# USB3_0HUB_1.net
KiCad netlist of a schematic drawn in Altium Designer
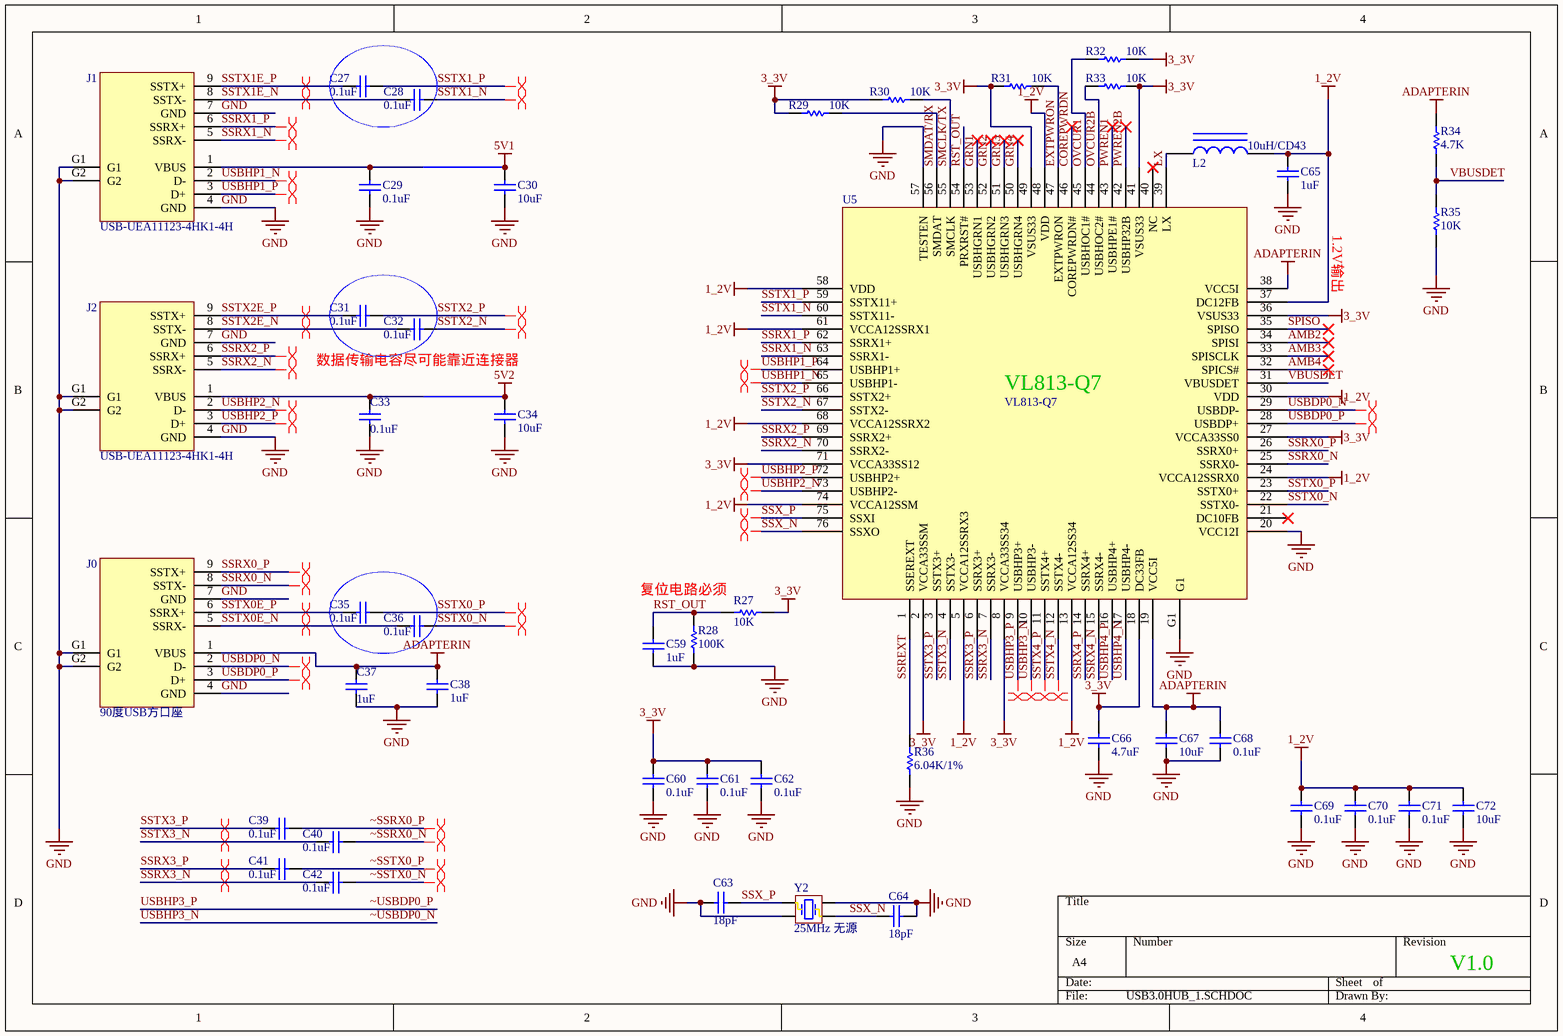
[diagram p0: USB3.0HUB_1.SCHDOC]

(export (version "E")
  (design (tool "Eeschema 10.0.6"))
  (components
    (comp (ref "C27")
      (value "0.1uF")
      (footprint "0603C")
      (description "Capacitor")
      (fields (field (name "PUBLISHER") "Altium Limited"))
      (libsource (lib "JL_SCH") (part "Cap"))
    )
    (comp (ref "C28")
      (value "0.1uF")
      (footprint "0603C")
      (description "Capacitor")
      (fields (field (name "PUBLISHER") "Altium Limited"))
      (libsource (lib "JL_SCH") (part "Cap"))
    )
    (comp (ref "C29")
      (value "0.1uF")
      (footprint "0603C")
      (description "Capacitor")
      (fields (field (name "PUBLISHER") "Altium Limited"))
      (libsource (lib "JL_SCH") (part "Cap"))
    )
    (comp (ref "C30")
      (value "10uF")
      (footprint "0805C")
      (description "Capacitor")
      (fields (field (name "PUBLISHER") "Altium Limited"))
      (libsource (lib "JL_SCH") (part "Cap"))
    )
    (comp (ref "C31")
      (value "0.1uF")
      (footprint "0603C")
      (description "Capacitor")
      (fields (field (name "PUBLISHER") "Altium Limited"))
      (libsource (lib "JL_SCH") (part "Cap"))
    )
    (comp (ref "C32")
      (value "0.1uF")
      (footprint "0603C")
      (description "Capacitor")
      (fields (field (name "PUBLISHER") "Altium Limited"))
      (libsource (lib "JL_SCH") (part "Cap"))
    )
    (comp (ref "C33")
      (value "0.1uF")
      (footprint "0603C")
      (description "Capacitor")
      (fields (field (name "PUBLISHER") "Altium Limited"))
      (libsource (lib "JL_SCH") (part "Cap"))
    )
    (comp (ref "C34")
      (value "10uF")
      (footprint "0805C")
      (description "Capacitor")
      (fields (field (name "PUBLISHER") "Altium Limited"))
      (libsource (lib "JL_SCH") (part "Cap"))
    )
    (comp (ref "C35")
      (value "0.1uF")
      (footprint "0603C")
      (description "Capacitor")
      (fields (field (name "PUBLISHER") "Altium Limited"))
      (libsource (lib "JL_SCH") (part "Cap"))
    )
    (comp (ref "C36")
      (value "0.1uF")
      (footprint "0603C")
      (description "Capacitor")
      (fields (field (name "PUBLISHER") "Altium Limited"))
      (libsource (lib "JL_SCH") (part "Cap"))
    )
    (comp (ref "C37")
      (value "1uF")
      (footprint "0603C")
      (description "Capacitor")
      (fields (field (name "PUBLISHER") "Altium Limited"))
      (libsource (lib "JL_SCH") (part "Cap"))
    )
    (comp (ref "C38")
      (value "1uF")
      (footprint "0603C")
      (description "Capacitor")
      (fields (field (name "PUBLISHER") "Altium Limited"))
      (libsource (lib "JL_SCH") (part "Cap"))
    )
    (comp (ref "C39")
      (value "0.1uF")
      (footprint "0603C")
      (description "Capacitor")
      (fields (field (name "PUBLISHER") "Altium Limited"))
      (libsource (lib "JL_SCH") (part "Cap"))
    )
    (comp (ref "C40")
      (value "0.1uF")
      (footprint "0603C")
      (description "Capacitor")
      (fields (field (name "PUBLISHER") "Altium Limited"))
      (libsource (lib "JL_SCH") (part "Cap"))
    )
    (comp (ref "C41")
      (value "0.1uF")
      (footprint "0603C")
      (description "Capacitor")
      (fields (field (name "PUBLISHER") "Altium Limited"))
      (libsource (lib "JL_SCH") (part "Cap"))
    )
    (comp (ref "C42")
      (value "0.1uF")
      (footprint "0603C")
      (description "Capacitor")
      (fields (field (name "PUBLISHER") "Altium Limited"))
      (libsource (lib "JL_SCH") (part "Cap"))
    )
    (comp (ref "C59")
      (value "1uF")
      (footprint "0603C")
      (description "Capacitor")
      (fields (field (name "PUBLISHER") "Altium Limited"))
      (libsource (lib "JL_SCH") (part "Cap"))
    )
    (comp (ref "C60")
      (value "0.1uF")
      (footprint "0603C")
      (description "Capacitor")
      (fields (field (name "PUBLISHER") "Altium Limited"))
      (libsource (lib "JL_SCH") (part "Cap"))
    )
    (comp (ref "C61")
      (value "0.1uF")
      (footprint "0603C")
      (description "Capacitor")
      (fields (field (name "PUBLISHER") "Altium Limited"))
      (libsource (lib "JL_SCH") (part "Cap"))
    )
    (comp (ref "C62")
      (value "0.1uF")
      (footprint "0603C")
      (description "Capacitor")
      (fields (field (name "PUBLISHER") "Altium Limited"))
      (libsource (lib "JL_SCH") (part "Cap"))
    )
    (comp (ref "C63")
      (value "18pF")
      (footprint "0603C")
      (description "Capacitor")
      (fields (field (name "PUBLISHER") "Altium Limited"))
      (libsource (lib "JL_SCH") (part "Cap"))
    )
    (comp (ref "C64")
      (value "18pF")
      (footprint "0603C")
      (description "Capacitor")
      (fields (field (name "PUBLISHER") "Altium Limited"))
      (libsource (lib "JL_SCH") (part "Cap"))
    )
    (comp (ref "C65")
      (value "1uF")
      (footprint "0603C")
      (description "Capacitor")
      (fields (field (name "PUBLISHER") "Altium Limited"))
      (libsource (lib "JL_SCH") (part "Cap"))
    )
    (comp (ref "C66")
      (value "4.7uF")
      (footprint "3216")
      (description "Capacitor")
      (fields (field (name "PUBLISHER") "Altium Limited"))
      (libsource (lib "JL_SCH") (part "Cap"))
    )
    (comp (ref "C67")
      (value "10uF")
      (footprint "3216")
      (description "Capacitor")
      (fields (field (name "PUBLISHER") "Altium Limited"))
      (libsource (lib "JL_SCH") (part "Cap"))
    )
    (comp (ref "C68")
      (value "0.1uF")
      (footprint "0603C")
      (description "Capacitor")
      (fields (field (name "PUBLISHER") "Altium Limited"))
      (libsource (lib "JL_SCH") (part "Cap"))
    )
    (comp (ref "C69")
      (value "0.1uF")
      (footprint "0603C")
      (description "Capacitor")
      (fields (field (name "PUBLISHER") "Altium Limited"))
      (libsource (lib "JL_SCH") (part "Cap"))
    )
    (comp (ref "C70")
      (value "0.1uF")
      (footprint "0603C")
      (description "Capacitor")
      (fields (field (name "PUBLISHER") "Altium Limited"))
      (libsource (lib "JL_SCH") (part "Cap"))
    )
    (comp (ref "C71")
      (value "0.1uF")
      (footprint "0603C")
      (description "Capacitor")
      (fields (field (name "PUBLISHER") "Altium Limited"))
      (libsource (lib "JL_SCH") (part "Cap"))
    )
    (comp (ref "C72")
      (value "10uF")
      (footprint "3216")
      (description "Capacitor")
      (fields (field (name "PUBLISHER") "Altium Limited"))
      (libsource (lib "JL_SCH") (part "Cap"))
    )
    (comp (ref "J0") (value "90度USB方口座") (footprint "USB-B-R") (libsource (lib "JL_SCH") (part "USB_DSP")))
    (comp (ref "J1")
      (value "USB-UEA11123-4HK1-4H")
      (footprint "USB3.0-A")
      (libsource (lib "JL_SCH") (part "USB_DSP"))
    )
    (comp (ref "J2")
      (value "USB-UEA11123-4HK1-4H")
      (footprint "USB3.0-A")
      (libsource (lib "JL_SCH") (part "USB_DSP"))
    )
    (comp (ref "L2")
      (value "10uH/CD43")
      (footprint "CD4532")
      (libsource (lib "JL_SCH") (part "INDUCTOR IRON"))
    )
    (comp (ref "R27")
      (value "10K")
      (footprint "0603R")
      (description "贴片电阻")
      (fields (field (name "PUBLISHER") "Altium Limited"))
      (libsource (lib "JL_SCH") (part "Res"))
    )
    (comp (ref "R28")
      (value "100K")
      (footprint "0603R")
      (description "贴片电阻")
      (fields (field (name "PUBLISHER") "Altium Limited"))
      (libsource (lib "JL_SCH") (part "Res"))
    )
    (comp (ref "R29")
      (value "10K")
      (footprint "0603R")
      (description "贴片电阻")
      (fields (field (name "PUBLISHER") "Altium Limited"))
      (libsource (lib "JL_SCH") (part "Res"))
    )
    (comp (ref "R30")
      (value "10K")
      (footprint "0603R")
      (description "贴片电阻")
      (fields (field (name "PUBLISHER") "Altium Limited"))
      (libsource (lib "JL_SCH") (part "Res"))
    )
    (comp (ref "R31")
      (value "10K")
      (footprint "0603R")
      (description "贴片电阻")
      (fields (field (name "PUBLISHER") "Altium Limited"))
      (libsource (lib "JL_SCH") (part "Res"))
    )
    (comp (ref "R32")
      (value "10K")
      (footprint "0603R")
      (description "贴片电阻")
      (fields (field (name "PUBLISHER") "Altium Limited"))
      (libsource (lib "JL_SCH") (part "Res"))
    )
    (comp (ref "R33")
      (value "10K")
      (footprint "0603R")
      (description "贴片电阻")
      (fields (field (name "PUBLISHER") "Altium Limited"))
      (libsource (lib "JL_SCH") (part "Res"))
    )
    (comp (ref "R34")
      (value "4.7K")
      (footprint "0603R")
      (description "贴片电阻")
      (fields (field (name "PUBLISHER") "Altium Limited"))
      (libsource (lib "JL_SCH") (part "Res"))
    )
    (comp (ref "R35")
      (value "10K")
      (footprint "0603R")
      (description "贴片电阻")
      (fields (field (name "PUBLISHER") "Altium Limited"))
      (libsource (lib "JL_SCH") (part "Res"))
    )
    (comp (ref "R36")
      (value "6.04K/1%")
      (footprint "0603R")
      (description "贴片电阻")
      (fields (field (name "PUBLISHER") "Altium Limited"))
      (libsource (lib "JL_SCH") (part "Res"))
    )
    (comp (ref "U5")
      (value "VL813-Q7")
      (footprint "QFN76-15P7-TH")
      (libsource (lib "JL_SCH") (part "VL812-Q7"))
    )
    (comp (ref "Y2")
      (value "25MHz 无源")
      (footprint "X3225")
      (description "Crystal Oscillator")
      (fields (field (name "PUBLISHER") "Altium Limited"))
      (libsource (lib "JL_SCH") (part "XTAL_1"))
    )
  )
  (nets
    (net (code "1") (name "/AMB2") (class "Default")
      (node (ref "U5") (pin "34") (pinfunction "SPISI_34") (pintype "passive+no_connect"))
    )
    (net (code "2") (name "/AMB3") (class "Default")
      (node (ref "U5") (pin "33") (pinfunction "SPISCLK_33") (pintype "passive+no_connect"))
    )
    (net (code "3") (name "/AMB4") (class "Default")
      (node (ref "U5") (pin "32") (pinfunction "SPICS#_32") (pintype "passive+no_connect"))
    )
    (net (code "4") (name "/COREPWRDN") (class "Default")
      (node (ref "U5") (pin "46") (pinfunction "COREPWRDN#_46") (pintype "passive+no_connect"))
    )
    (net (code "5") (name "/EXTPWRON") (class "Default")
      (node (ref "R31") (pin "2") (pinfunction "2_2") (pintype "passive"))
      (node (ref "U5") (pin "47") (pinfunction "EXTPWRON_47") (pintype "passive"))
    )
    (net (code "6") (name "/GRN1") (class "Default")
      (node (ref "U5") (pin "53") (pinfunction "USBHGRN1_53") (pintype "passive+no_connect"))
    )
    (net (code "7") (name "/GRN2") (class "Default")
      (node (ref "U5") (pin "52") (pinfunction "USBHGRN2_52") (pintype "passive+no_connect"))
    )
    (net (code "8") (name "/GRN3") (class "Default")
      (node (ref "U5") (pin "51") (pinfunction "USBHGRN3_51") (pintype "passive+no_connect"))
    )
    (net (code "9") (name "/GRN4") (class "Default")
      (node (ref "U5") (pin "50") (pinfunction "USBHGRN4_50") (pintype "passive+no_connect"))
    )
    (net (code "10") (name "/LX") (class "Default")
      (node (ref "L2") (pin "1") (pinfunction "1_1") (pintype "passive"))
      (node (ref "U5") (pin "39") (pinfunction "LX_39") (pintype "passive"))
    )
    (net (code "11") (name "/OVCUR1") (class "Default")
      (node (ref "R32") (pin "2") (pinfunction "2_2") (pintype "passive"))
      (node (ref "U5") (pin "45") (pinfunction "USBHOC1#_45") (pintype "passive"))
    )
    (net (code "12") (name "/OVCUR2B") (class "Default")
      (node (ref "R33") (pin "2") (pinfunction "2_2") (pintype "passive"))
      (node (ref "U5") (pin "44") (pinfunction "USBHOC2#_44") (pintype "passive"))
    )
    (net (code "13") (name "/PWREN1") (class "Default")
      (node (ref "U5") (pin "43") (pinfunction "USBHPE1#_43") (pintype "passive+no_connect"))
    )
    (net (code "14") (name "/PWREN2B") (class "Default")
      (node (ref "U5") (pin "42") (pinfunction "USBHP32B_42") (pintype "passive+no_connect"))
    )
    (net (code "15") (name "/RST_OUT") (class "Default")
      (node (ref "C59") (pin "2") (pinfunction "2_2") (pintype "passive"))
      (node (ref "R27") (pin "2") (pinfunction "2_2") (pintype "passive"))
      (node (ref "R28") (pin "1") (pinfunction "1_1") (pintype "passive"))
      (node (ref "U5") (pin "54") (pinfunction "PRXRST#_54") (pintype "passive"))
    )
    (net (code "16") (name "/SMCLK{slash}TX") (class "Default")
      (node (ref "R30") (pin "2") (pinfunction "2_2") (pintype "passive"))
      (node (ref "U5") (pin "55") (pinfunction "SMCLK_55") (pintype "passive"))
    )
    (net (code "17") (name "/SMDAT{slash}RX") (class "Default")
      (node (ref "R29") (pin "2") (pinfunction "2_2") (pintype "passive"))
      (node (ref "U5") (pin "56") (pinfunction "SMDAT_56") (pintype "passive"))
    )
    (net (code "18") (name "/SPISO") (class "Default")
      (node (ref "U5") (pin "35") (pinfunction "SPISO_35") (pintype "passive+no_connect"))
    )
    (net (code "19") (name "/SSREXT") (class "Default")
      (node (ref "R36") (pin "1") (pinfunction "1_1") (pintype "passive"))
      (node (ref "U5") (pin "1") (pinfunction "SSEREXT_1") (pintype "passive"))
    )
    (net (code "20") (name "/SSRX0_N") (class "Default")
      (node (ref "J0") (pin "8") (pinfunction "SSTX-_8") (pintype "passive"))
      (node (ref "U5") (pin "25") (pinfunction "SSRX0-_25") (pintype "passive"))
    )
    (net (code "21") (name "/SSRX0_P") (class "Default")
      (node (ref "J0") (pin "9") (pinfunction "SSTX+_9") (pintype "passive"))
      (node (ref "U5") (pin "26") (pinfunction "SSRX0+_26") (pintype "passive"))
    )
    (net (code "22") (name "/SSRX1_N") (class "Default")
      (node (ref "J1") (pin "5") (pinfunction "SSRX-_5") (pintype "passive"))
      (node (ref "U5") (pin "63") (pinfunction "SSRX1-_63") (pintype "passive"))
    )
    (net (code "23") (name "/SSRX1_P") (class "Default")
      (node (ref "J1") (pin "6") (pinfunction "SSRX+_6") (pintype "passive"))
      (node (ref "U5") (pin "62") (pinfunction "SSRX1+_62") (pintype "passive"))
    )
    (net (code "24") (name "/SSRX2_N") (class "Default")
      (node (ref "J2") (pin "5") (pinfunction "SSRX-_5") (pintype "passive"))
      (node (ref "U5") (pin "70") (pinfunction "SSRX2-_70") (pintype "passive"))
    )
    (net (code "25") (name "/SSRX2_P") (class "Default")
      (node (ref "J2") (pin "6") (pinfunction "SSRX+_6") (pintype "passive"))
      (node (ref "U5") (pin "69") (pinfunction "SSRX2+_69") (pintype "passive"))
    )
    (net (code "26") (name "/SSRX3_N") (class "Default")
      (node (ref "C42") (pin "2") (pinfunction "2_2") (pintype "passive"))
      (node (ref "U5") (pin "7") (pinfunction "SSRX3-_7") (pintype "passive"))
    )
    (net (code "27") (name "/SSRX3_P") (class "Default")
      (node (ref "C41") (pin "2") (pinfunction "2_2") (pintype "passive"))
      (node (ref "U5") (pin "6") (pinfunction "SSRX3+_6") (pintype "passive"))
    )
    (net (code "28") (name "/SSRX4_N") (class "Default")
      (node (ref "U5") (pin "15") (pinfunction "SSRX4-_15") (pintype "passive"))
    )
    (net (code "29") (name "/SSRX4_P") (class "Default")
      (node (ref "U5") (pin "14") (pinfunction "SSRX4+_14") (pintype "passive"))
    )
    (net (code "30") (name "/SSTX0E_N") (class "Default")
      (node (ref "C36") (pin "2") (pinfunction "2_2") (pintype "passive"))
      (node (ref "J0") (pin "5") (pinfunction "SSRX-_5") (pintype "passive"))
    )
    (net (code "31") (name "/SSTX0E_P") (class "Default")
      (node (ref "C35") (pin "2") (pinfunction "2_2") (pintype "passive"))
      (node (ref "J0") (pin "6") (pinfunction "SSRX+_6") (pintype "passive"))
    )
    (net (code "32") (name "/SSTX0_N") (class "Default")
      (node (ref "C36") (pin "1") (pinfunction "1_1") (pintype "passive"))
      (node (ref "U5") (pin "22") (pinfunction "SSTX0-_22") (pintype "passive"))
    )
    (net (code "33") (name "/SSTX0_P") (class "Default")
      (node (ref "C35") (pin "1") (pinfunction "1_1") (pintype "passive"))
      (node (ref "U5") (pin "23") (pinfunction "SSTX0+_23") (pintype "passive"))
    )
    (net (code "34") (name "/SSTX1E_N") (class "Default")
      (node (ref "C28") (pin "2") (pinfunction "2_2") (pintype "passive"))
      (node (ref "J1") (pin "8") (pinfunction "SSTX-_8") (pintype "passive"))
    )
    (net (code "35") (name "/SSTX1E_P") (class "Default")
      (node (ref "C27") (pin "2") (pinfunction "2_2") (pintype "passive"))
      (node (ref "J1") (pin "9") (pinfunction "SSTX+_9") (pintype "passive"))
    )
    (net (code "36") (name "/SSTX1_N") (class "Default")
      (node (ref "C28") (pin "1") (pinfunction "1_1") (pintype "passive"))
      (node (ref "U5") (pin "60") (pinfunction "SSTX11-_60") (pintype "passive"))
    )
    (net (code "37") (name "/SSTX1_P") (class "Default")
      (node (ref "C27") (pin "1") (pinfunction "1_1") (pintype "passive"))
      (node (ref "U5") (pin "59") (pinfunction "SSTX11+_59") (pintype "passive"))
    )
    (net (code "38") (name "/SSTX2E_N") (class "Default")
      (node (ref "C32") (pin "2") (pinfunction "2_2") (pintype "passive"))
      (node (ref "J2") (pin "8") (pinfunction "SSTX-_8") (pintype "passive"))
    )
    (net (code "39") (name "/SSTX2E_P") (class "Default")
      (node (ref "C31") (pin "2") (pinfunction "2_2") (pintype "passive"))
      (node (ref "J2") (pin "9") (pinfunction "SSTX+_9") (pintype "passive"))
    )
    (net (code "40") (name "/SSTX2_N") (class "Default")
      (node (ref "C32") (pin "1") (pinfunction "1_1") (pintype "passive"))
      (node (ref "U5") (pin "67") (pinfunction "SSTX2-_67") (pintype "passive"))
    )
    (net (code "41") (name "/SSTX2_P") (class "Default")
      (node (ref "C31") (pin "1") (pinfunction "1_1") (pintype "passive"))
      (node (ref "U5") (pin "66") (pinfunction "SSTX2+_66") (pintype "passive"))
    )
    (net (code "42") (name "/SSTX3_N") (class "Default")
      (node (ref "C40") (pin "2") (pinfunction "2_2") (pintype "passive"))
      (node (ref "U5") (pin "4") (pinfunction "SSTX3-_4") (pintype "passive"))
    )
    (net (code "43") (name "/SSTX3_P") (class "Default")
      (node (ref "C39") (pin "2") (pinfunction "2_2") (pintype "passive"))
      (node (ref "U5") (pin "3") (pinfunction "SSTX3+_3") (pintype "passive"))
    )
    (net (code "44") (name "/SSTX4_N") (class "Default")
      (node (ref "U5") (pin "12") (pinfunction "SSTX4-_12") (pintype "passive"))
    )
    (net (code "45") (name "/SSTX4_P") (class "Default")
      (node (ref "U5") (pin "11") (pinfunction "SSTX4+_11") (pintype "passive"))
    )
    (net (code "46") (name "/SSX_N") (class "Default")
      (node (ref "C64") (pin "2") (pinfunction "2_2") (pintype "passive"))
      (node (ref "U5") (pin "76") (pinfunction "SSXO_76") (pintype "passive"))
      (node (ref "Y2") (pin "3") (pinfunction "OSC2_3") (pintype "passive"))
    )
    (net (code "47") (name "/SSX_P") (class "Default")
      (node (ref "C63") (pin "2") (pinfunction "2_2") (pintype "passive"))
      (node (ref "U5") (pin "75") (pinfunction "SSXI_75") (pintype "passive"))
      (node (ref "Y2") (pin "1") (pinfunction "OSC1_1") (pintype "passive"))
    )
    (net (code "48") (name "/USBDP0_N") (class "Default")
      (node (ref "J0") (pin "2") (pinfunction "D-_2") (pintype "passive"))
      (node (ref "U5") (pin "29") (pinfunction "USBDP-_29") (pintype "passive"))
    )
    (net (code "49") (name "/USBDP0_P") (class "Default")
      (node (ref "J0") (pin "3") (pinfunction "D+_3") (pintype "passive"))
      (node (ref "U5") (pin "28") (pinfunction "USBDP+_28") (pintype "passive"))
    )
    (net (code "50") (name "/USBHP1_N") (class "Default")
      (node (ref "J1") (pin "2") (pinfunction "D-_2") (pintype "passive"))
      (node (ref "U5") (pin "65") (pinfunction "USBHP1-_65") (pintype "passive"))
    )
    (net (code "51") (name "/USBHP1_P") (class "Default")
      (node (ref "J1") (pin "3") (pinfunction "D+_3") (pintype "passive"))
      (node (ref "U5") (pin "64") (pinfunction "USBHP1+_64") (pintype "passive"))
    )
    (net (code "52") (name "/USBHP2_N") (class "Default")
      (node (ref "J2") (pin "2") (pinfunction "D-_2") (pintype "passive"))
      (node (ref "U5") (pin "73") (pinfunction "USBHP2-_73") (pintype "passive"))
    )
    (net (code "53") (name "/USBHP2_P") (class "Default")
      (node (ref "J2") (pin "3") (pinfunction "D+_3") (pintype "passive"))
      (node (ref "U5") (pin "72") (pinfunction "USBHP2+_72") (pintype "passive"))
    )
    (net (code "54") (name "/USBHP3_N") (class "Default")
      (node (ref "U5") (pin "10") (pinfunction "USBHP3-_10") (pintype "passive"))
    )
    (net (code "55") (name "/USBHP3_P") (class "Default")
      (node (ref "U5") (pin "9") (pinfunction "USBHP3+_9") (pintype "passive"))
    )
    (net (code "56") (name "/USBHP4_N") (class "Default")
      (node (ref "U5") (pin "17") (pinfunction "USBHP4-_17") (pintype "passive"))
    )
    (net (code "57") (name "/USBHP4_P") (class "Default")
      (node (ref "U5") (pin "16") (pinfunction "USBHP4+_16") (pintype "passive"))
    )
    (net (code "59") (name "/VBUSDET") (class "Default")
      (node (ref "R34") (pin "2") (pinfunction "2_2") (pintype "passive"))
      (node (ref "R35") (pin "1") (pinfunction "1_1") (pintype "passive"))
      (node (ref "U5") (pin "31") (pinfunction "VBUSDET_31") (pintype "passive"))
    )
    (net (code "61") (name "/~SSRX0_N") (class "Default")
      (node (ref "C40") (pin "1") (pinfunction "1_1") (pintype "passive"))
    )
    (net (code "62") (name "/~SSRX0_P") (class "Default")
      (node (ref "C39") (pin "1") (pinfunction "1_1") (pintype "passive"))
    )
    (net (code "63") (name "/~SSTX0_N") (class "Default")
      (node (ref "C42") (pin "1") (pinfunction "1_1") (pintype "passive"))
    )
    (net (code "64") (name "/~SSTX0_P") (class "Default")
      (node (ref "C41") (pin "1") (pinfunction "1_1") (pintype "passive"))
    )
    (net (code "65") (name "1_2V") (class "Default")
      (node (ref "C65") (pin "2") (pinfunction "2_2") (pintype "passive"))
      (node (ref "C69") (pin "2") (pinfunction "2_2") (pintype "passive"))
      (node (ref "C70") (pin "2") (pinfunction "2_2") (pintype "passive"))
      (node (ref "C71") (pin "2") (pinfunction "2_2") (pintype "passive"))
      (node (ref "C72") (pin "1") (pinfunction "1_1") (pintype "passive"))
      (node (ref "L2") (pin "2") (pinfunction "2_2") (pintype "passive"))
      (node (ref "U5") (pin "13") (pinfunction "VCCA12SS34_13") (pintype "passive"))
      (node (ref "U5") (pin "24") (pinfunction "VCCA12SSRX0_24") (pintype "passive"))
      (node (ref "U5") (pin "30") (pinfunction "VDD_30") (pintype "passive"))
      (node (ref "U5") (pin "37") (pinfunction "DC12FB_37") (pintype "passive"))
      (node (ref "U5") (pin "48") (pinfunction "VDD_48") (pintype "passive"))
      (node (ref "U5") (pin "5") (pinfunction "VCCA12SSRX3_5") (pintype "passive"))
      (node (ref "U5") (pin "58") (pinfunction "VDD_58") (pintype "passive"))
      (node (ref "U5") (pin "61") (pinfunction "VCCA12SSRX1_61") (pintype "passive"))
      (node (ref "U5") (pin "68") (pinfunction "VCCA12SSRX2_68") (pintype "passive"))
      (node (ref "U5") (pin "74") (pinfunction "VCCA12SSM_74") (pintype "passive"))
    )
    (net (code "66") (name "3_3V") (class "Default")
      (node (ref "C60") (pin "2") (pinfunction "2_2") (pintype "passive"))
      (node (ref "C61") (pin "2") (pinfunction "2_2") (pintype "passive"))
      (node (ref "C62") (pin "2") (pinfunction "2_2") (pintype "passive"))
      (node (ref "C66") (pin "1") (pinfunction "1_1") (pintype "passive"))
      (node (ref "R27") (pin "1") (pinfunction "1_1") (pintype "passive"))
      (node (ref "R29") (pin "1") (pinfunction "1_1") (pintype "passive"))
      (node (ref "R30") (pin "1") (pinfunction "1_1") (pintype "passive"))
      (node (ref "R31") (pin "1") (pinfunction "1_1") (pintype "passive"))
      (node (ref "R32") (pin "1") (pinfunction "1_1") (pintype "passive"))
      (node (ref "R33") (pin "1") (pinfunction "1_1") (pintype "passive"))
      (node (ref "U5") (pin "18") (pinfunction "DC33FB_18") (pintype "passive"))
      (node (ref "U5") (pin "2") (pinfunction "VCCA33SSM_2") (pintype "passive"))
      (node (ref "U5") (pin "27") (pinfunction "VCCA33SS0_27") (pintype "passive"))
      (node (ref "U5") (pin "36") (pinfunction "VSUS33_36") (pintype "passive"))
      (node (ref "U5") (pin "41") (pinfunction "VSUS33_41") (pintype "passive"))
      (node (ref "U5") (pin "49") (pinfunction "VSUS33_49") (pintype "passive"))
      (node (ref "U5") (pin "71") (pinfunction "VCCA33SS12_71") (pintype "passive"))
      (node (ref "U5") (pin "8") (pinfunction "VCCA33SS34_8") (pintype "passive"))
    )
    (net (code "67") (name "5V1") (class "Default")
      (node (ref "C29") (pin "2") (pinfunction "2_2") (pintype "passive"))
      (node (ref "C30") (pin "1") (pinfunction "1_1") (pintype "passive"))
      (node (ref "J1") (pin "1") (pinfunction "VBUS_1") (pintype "passive"))
    )
    (net (code "68") (name "5V2") (class "Default")
      (node (ref "C33") (pin "2") (pinfunction "2_2") (pintype "passive"))
      (node (ref "C34") (pin "1") (pinfunction "1_1") (pintype "passive"))
      (node (ref "J2") (pin "1") (pinfunction "VBUS_1") (pintype "passive"))
    )
    (net (code "69") (name "ADAPTERIN") (class "Default")
      (node (ref "C37") (pin "2") (pinfunction "2_2") (pintype "passive"))
      (node (ref "C38") (pin "2") (pinfunction "2_2") (pintype "passive"))
      (node (ref "C67") (pin "1") (pinfunction "1_1") (pintype "passive"))
      (node (ref "C68") (pin "2") (pinfunction "2_2") (pintype "passive"))
      (node (ref "J0") (pin "1") (pinfunction "VBUS_1") (pintype "passive"))
      (node (ref "R34") (pin "1") (pinfunction "1_1") (pintype "passive"))
      (node (ref "U5") (pin "19") (pinfunction "VCC5I_19") (pintype "passive"))
      (node (ref "U5") (pin "38") (pinfunction "VCC5I_38") (pintype "passive"))
    )
    (net (code "70") (name "GND") (class "Default")
      (node (ref "C29") (pin "1") (pinfunction "1_1") (pintype "passive"))
      (node (ref "C30") (pin "2") (pinfunction "2_2") (pintype "passive"))
      (node (ref "C33") (pin "1") (pinfunction "1_1") (pintype "passive"))
      (node (ref "C34") (pin "2") (pinfunction "2_2") (pintype "passive"))
      (node (ref "C37") (pin "1") (pinfunction "1_1") (pintype "passive"))
      (node (ref "C38") (pin "1") (pinfunction "1_1") (pintype "passive"))
      (node (ref "C59") (pin "1") (pinfunction "1_1") (pintype "passive"))
      (node (ref "C60") (pin "1") (pinfunction "1_1") (pintype "passive"))
      (node (ref "C61") (pin "1") (pinfunction "1_1") (pintype "passive"))
      (node (ref "C62") (pin "1") (pinfunction "1_1") (pintype "passive"))
      (node (ref "C63") (pin "1") (pinfunction "1_1") (pintype "passive"))
      (node (ref "C64") (pin "1") (pinfunction "1_1") (pintype "passive"))
      (node (ref "C65") (pin "1") (pinfunction "1_1") (pintype "passive"))
      (node (ref "C66") (pin "2") (pinfunction "2_2") (pintype "passive"))
      (node (ref "C67") (pin "2") (pinfunction "2_2") (pintype "passive"))
      (node (ref "C68") (pin "1") (pinfunction "1_1") (pintype "passive"))
      (node (ref "C69") (pin "1") (pinfunction "1_1") (pintype "passive"))
      (node (ref "C70") (pin "1") (pinfunction "1_1") (pintype "passive"))
      (node (ref "C71") (pin "1") (pinfunction "1_1") (pintype "passive"))
      (node (ref "C72") (pin "2") (pinfunction "2_2") (pintype "passive"))
      (node (ref "J0") (pin "4") (pinfunction "GND_4") (pintype "passive"))
      (node (ref "J0") (pin "7") (pinfunction "GND_7") (pintype "passive"))
      (node (ref "J0") (pin "G1") (pinfunction "G1_G1") (pintype "passive"))
      (node (ref "J0") (pin "G2") (pinfunction "G2_G2") (pintype "passive"))
      (node (ref "J1") (pin "4") (pinfunction "GND_4") (pintype "passive"))
      (node (ref "J1") (pin "7") (pinfunction "GND_7") (pintype "passive"))
      (node (ref "J1") (pin "G1") (pinfunction "G1_G1") (pintype "passive"))
      (node (ref "J1") (pin "G2") (pinfunction "G2_G2") (pintype "passive"))
      (node (ref "J2") (pin "4") (pinfunction "GND_4") (pintype "passive"))
      (node (ref "J2") (pin "7") (pinfunction "GND_7") (pintype "passive"))
      (node (ref "J2") (pin "G1") (pinfunction "G1_G1") (pintype "passive"))
      (node (ref "J2") (pin "G2") (pinfunction "G2_G2") (pintype "passive"))
      (node (ref "R28") (pin "2") (pinfunction "2_2") (pintype "passive"))
      (node (ref "R35") (pin "2") (pinfunction "2_2") (pintype "passive"))
      (node (ref "R36") (pin "2") (pinfunction "2_2") (pintype "passive"))
      (node (ref "U5") (pin "20") (pinfunction "VCC12I_20") (pintype "passive"))
      (node (ref "U5") (pin "57") (pinfunction "TESTEN_57") (pintype "passive"))
      (node (ref "U5") (pin "G1") (pinfunction "G1_G1") (pintype "passive"))
      (node (ref "Y2") (pin "2") (pinfunction "NA_2") (pintype "passive"))
      (node (ref "Y2") (pin "4") (pinfunction "NA_4") (pintype "passive"))
    )
    (net (code "71") (name "unconnected-(U5-DC10FB-Pad21)") (class "Default")
      (node (ref "U5") (pin "21") (pinfunction "DC10FB_21") (pintype "passive+no_connect"))
    )
    (net (code "72") (name "unconnected-(U5-NC-Pad40)") (class "Default")
      (node (ref "U5") (pin "40") (pinfunction "NC_40") (pintype "passive+no_connect"))
    )
  )
)
